# weather-cube_piezo_overvoltage_protectio.net
KiCad netlist of a schematic drawn in EAGLE
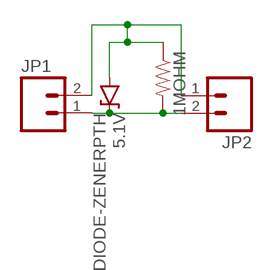
[diagram p0: schematic, sheet 1]

(export (version "E")
  (design (tool "Eeschema 10.0.6"))
  (components
    (comp (ref "1MOHM")
      (value "RESISTORAXIAL-0.3")
      (footprint "eagle-import:AXIAL-0.3")
      (libsource (lib "eagle-import") (part "RESISTORAXIAL-0.3"))
    )
    (comp (ref "5.1V")
      (value "DIODE-ZENERPTH")
      (footprint "eagle-import:DIODE-ZENER")
      (libsource (lib "eagle-import") (part "DIODE-ZENERPTH"))
    )
    (comp (ref "JP1")
      (value "M02PTH")
      (footprint "eagle-import:1X02")
      (libsource (lib "eagle-import") (part "M02PTH"))
    )
    (comp (ref "JP2")
      (value "M02PTH")
      (footprint "eagle-import:1X02")
      (libsource (lib "eagle-import") (part "M02PTH"))
    )
  )
  (nets
    (net (code "1") (name "Net-(1MOHM-1)") (class "Default")
      (node (ref "1MOHM") (pin "P$1") (pinfunction "1_P$1") (pintype "passive"))
      (node (ref "5.1V") (pin "P$2") (pinfunction "A_P$2") (pintype "passive"))
      (node (ref "JP1") (pin "2") (pinfunction "2_2") (pintype "passive"))
      (node (ref "JP2") (pin "1") (pinfunction "1_1") (pintype "passive"))
    )
    (net (code "2") (name "Net-(1MOHM-2)") (class "Default")
      (node (ref "1MOHM") (pin "P$2") (pinfunction "2_P$2") (pintype "passive"))
      (node (ref "5.1V") (pin "P$1") (pinfunction "C_P$1") (pintype "passive"))
      (node (ref "JP1") (pin "1") (pinfunction "1_1") (pintype "passive"))
      (node (ref "JP2") (pin "2") (pinfunction "2_2") (pintype "passive"))
    )
  )
)
